# BopITSchematic.net
KiCad netlist of a schematic drawn in Altium Designer
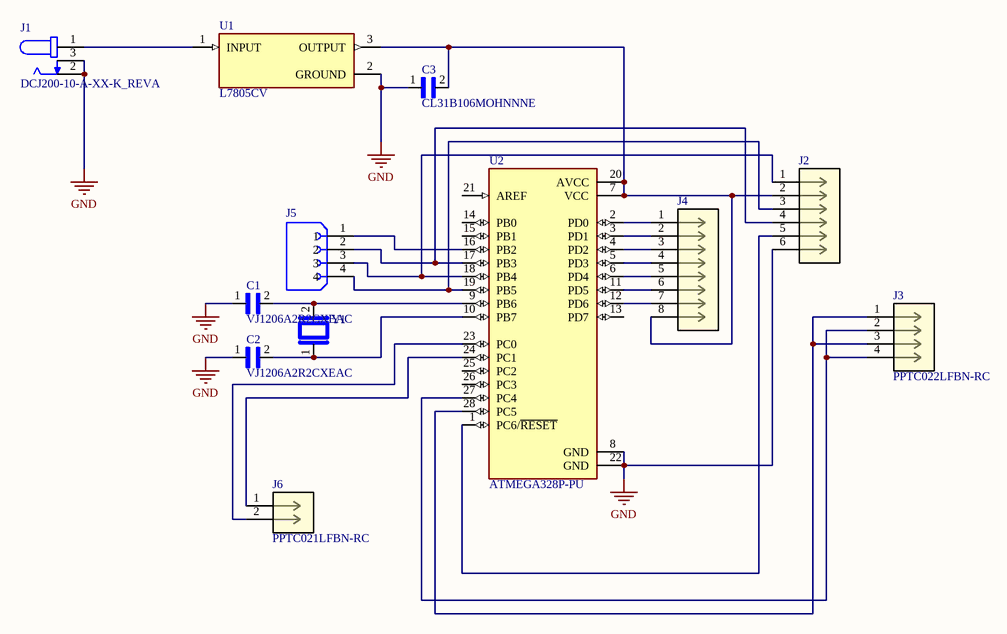
[diagram p0: BopITSchematic.SchDoc]

(export (version "E")
  (design (tool "Eeschema 10.0.6"))
  (components
    (comp (ref "C1")
      (value "VJ1206A2R2CXEAC")
      (footprint "CAPC3216X170N")
      (libsource (lib "VJ1206A2R2CXEAC") (part "VJ1206A2R2CXEAC"))
    )
    (comp (ref "C2")
      (value "VJ1206A2R2CXEAC")
      (footprint "CAPC3216X170N")
      (libsource (lib "VJ1206A2R2CXEAC") (part "VJ1206A2R2CXEAC"))
    )
    (comp (ref "C3")
      (value "CL31B106MOHNNNE")
      (footprint "CAPC3216X140N")
      (libsource (lib "CL31B106MOHNNNE") (part "CL31B106MOHNNNE"))
    )
    (comp (ref "J1")
      (value "DCJ200-10-A-XX-K_REVA")
      (footprint "GCT_DCJ200-10-A-XX-K_REVA")
      (description "Power Barrel Connector Jack 2.05mm ID (0.081), 5.50mm OD (0.217) Through Hole, Right Angle")
      (fields (field (name "MF") "Global Connector Technology") (field (name "MP") "DCJ200-10-A-K1-K"))
      (libsource (lib "DCJ200-10-A-XX-K_REVA") (part "DCJ200-10-A-XX-K_REVA"))
    )
    (comp (ref "J2")
      (value "61300621121")
      (footprint "CONN06_6130_7P62X5P08_WRE")
      (description "No Description Available")
      (libsource (lib "61300621121") (part "61300621121"))
    )
    (comp (ref "J3")
      (value "PPTC022LFBN-RC")
      (footprint "CONN_PPTC022LFBN-RC_SUL")
      (description "No Description Available")
      (libsource (lib "PPTC022LFBN-RC") (part "PPTC022LFBN-RC"))
    )
    (comp (ref "J4")
      (value "PPTC081LFBN-RC")
      (footprint "CONN_PPTC081LFBN-RC_SUL")
      (description "No Description Available")
      (libsource (lib "PPTC081LFBN-RC") (part "PPTC081LFBN-RC"))
    )
    (comp (ref "J5")
      (value "PPTC041LFBN-RC")
      (footprint "SULLINS_PPTC041LFBN-RC")
      (description "4 Position Header Connector 0.100 (2.54mm) Through Hole Tin")
      (fields (field (name "MF") "Sullins Connector") (field (name "DIGI-KEY_PART_NUMBER") "S7002-ND"))
      (libsource (lib "PPTC041LFBN-RC") (part "PPTC041LFBN-RC"))
    )
    (comp (ref "J6")
      (value "PPTC021LFBN-RC")
      (footprint "CONN2_LFBN-RC_SUL")
      (description "No Description Available")
      (libsource (lib "PPTC021LFBN-RC") (part "PPTC021LFBN-RC"))
    )
    (comp (ref "U1")
      (value "L7805CV")
      (footprint "TO255P1040X460X1968-3")
      (description "Linear Voltage Regulator IC Positive Fixed 1 Output 1.5A TO-220")
      (fields (field (name "MF") "STMicroelectronics"))
      (libsource (lib "L7805CV") (part "L7805CV"))
    )
    (comp (ref "U2")
      (value "ATMEGA328P-PU")
      (footprint "DIP794W46P254L2967H457Q28B")
      (description "ATmega Series 20 MHz 32 KB Flash 2 KB SRAM 8-Bit Microcontroller - DIP-28")
      (libsource (lib "ATMEGA328P-PU") (part "ATMEGA328P-PU"))
    )
    (comp (ref "Y1")
      (value "HC-49/U-S16000000ABJB")
      (footprint "XTAL_HC49P488W43L1150T466H350")
      (description "16 MHz Â±30ppm Crystal 18pF 50 Ohms HC-49/US")
      (fields (field (name "MF") "Citizen Finedevice Co Ltd"))
      (libsource (lib "HC-49_U-S16000000ABJB") (part "HC-49/U-S16000000ABJB"))
    )
  )
  (nets
    (net (code "1") (name "GND") (class "Default")
      (node (ref "C1") (pin "1") (pinfunction "1_1") (pintype "passive"))
      (node (ref "C2") (pin "1") (pinfunction "1_1") (pintype "passive"))
      (node (ref "C3") (pin "1") (pinfunction "1_1") (pintype "passive"))
      (node (ref "J1") (pin "2") (pinfunction "2_2") (pintype "passive"))
      (node (ref "J1") (pin "3") (pinfunction "3_3") (pintype "passive"))
      (node (ref "J2") (pin "6") (pinfunction "6_6") (pintype "passive"))
      (node (ref "U1") (pin "2") (pinfunction "GROUND_2") (pintype "power_in"))
      (node (ref "U2") (pin "22") (pinfunction "GND_22") (pintype "power_in"))
      (node (ref "U2") (pin "8") (pinfunction "GND_8") (pintype "power_in"))
    )
    (net (code "2") (name "Net-(U1-INPUT)") (class "Default")
      (node (ref "J1") (pin "1") (pinfunction "1_1") (pintype "passive"))
      (node (ref "U1") (pin "1") (pinfunction "INPUT_1") (pintype "input"))
    )
    (net (code "3") (name "Net-(U1-OUTPUT)") (class "Default")
      (node (ref "C3") (pin "2") (pinfunction "2_2") (pintype "passive"))
      (node (ref "J2") (pin "2") (pinfunction "2_2") (pintype "passive"))
      (node (ref "J4") (pin "8") (pinfunction "8_8") (pintype "passive"))
      (node (ref "U1") (pin "3") (pinfunction "OUTPUT_3") (pintype "output"))
      (node (ref "U2") (pin "20") (pinfunction "AVCC_20") (pintype "power_in"))
      (node (ref "U2") (pin "7") (pinfunction "VCC_7") (pintype "power_in"))
    )
    (net (code "4") (name "Net-(U2-PB2)") (class "Default")
      (node (ref "J5") (pin "1") (pinfunction "1_1") (pintype "passive"))
      (node (ref "U2") (pin "16") (pinfunction "PB2_16") (pintype "bidirectional"))
    )
    (net (code "5") (name "Net-(U2-PB3)") (class "Default")
      (node (ref "J2") (pin "4") (pinfunction "4_4") (pintype "passive"))
      (node (ref "J5") (pin "2") (pinfunction "2_2") (pintype "passive"))
      (node (ref "U2") (pin "17") (pinfunction "PB3_17") (pintype "bidirectional"))
    )
    (net (code "6") (name "Net-(U2-PB4)") (class "Default")
      (node (ref "J2") (pin "1") (pinfunction "1_1") (pintype "passive"))
      (node (ref "J5") (pin "3") (pinfunction "3_3") (pintype "passive"))
      (node (ref "U2") (pin "18") (pinfunction "PB4_18") (pintype "bidirectional"))
    )
    (net (code "7") (name "Net-(U2-PB5)") (class "Default")
      (node (ref "J2") (pin "3") (pinfunction "3_3") (pintype "passive"))
      (node (ref "J5") (pin "4") (pinfunction "4_4") (pintype "passive"))
      (node (ref "U2") (pin "19") (pinfunction "PB5_19") (pintype "bidirectional"))
    )
    (net (code "8") (name "Net-(U2-PB6)") (class "Default")
      (node (ref "C1") (pin "2") (pinfunction "2_2") (pintype "passive"))
      (node (ref "U2") (pin "9") (pinfunction "PB6_9") (pintype "bidirectional"))
      (node (ref "Y1") (pin "2") (pinfunction "2_2") (pintype "passive"))
    )
    (net (code "9") (name "Net-(U2-PB7)") (class "Default")
      (node (ref "C2") (pin "2") (pinfunction "2_2") (pintype "passive"))
      (node (ref "U2") (pin "10") (pinfunction "PB7_10") (pintype "bidirectional"))
      (node (ref "Y1") (pin "1") (pinfunction "1_1") (pintype "passive"))
    )
    (net (code "10") (name "Net-(U2-PC0)") (class "Default")
      (node (ref "J6") (pin "2") (pinfunction "2_2") (pintype "passive"))
      (node (ref "U2") (pin "23") (pinfunction "PC0_23") (pintype "bidirectional"))
    )
    (net (code "11") (name "Net-(U2-PC1)") (class "Default")
      (node (ref "J6") (pin "1") (pinfunction "1_1") (pintype "passive"))
      (node (ref "U2") (pin "24") (pinfunction "PC1_24") (pintype "bidirectional"))
    )
    (net (code "12") (name "Net-(U2-PC4)") (class "Default")
      (node (ref "J3") (pin "2") (pinfunction "2_2") (pintype "passive"))
      (node (ref "J3") (pin "4") (pinfunction "4_4") (pintype "passive"))
      (node (ref "U2") (pin "27") (pinfunction "PC4_27") (pintype "bidirectional"))
    )
    (net (code "13") (name "Net-(U2-PC5)") (class "Default")
      (node (ref "J3") (pin "1") (pinfunction "1_1") (pintype "passive"))
      (node (ref "J3") (pin "3") (pinfunction "3_3") (pintype "passive"))
      (node (ref "U2") (pin "28") (pinfunction "PC5_28") (pintype "bidirectional"))
    )
    (net (code "14") (name "Net-(U2-PC6{slash}~{RESET})") (class "Default")
      (node (ref "J2") (pin "5") (pinfunction "5_5") (pintype "passive"))
      (node (ref "U2") (pin "1") (pinfunction "PC6/~{RESET}_1") (pintype "bidirectional"))
    )
    (net (code "15") (name "Net-(U2-PD0)") (class "Default")
      (node (ref "J4") (pin "1") (pinfunction "1_1") (pintype "passive"))
      (node (ref "U2") (pin "2") (pinfunction "PD0_2") (pintype "bidirectional"))
    )
    (net (code "16") (name "Net-(U2-PD1)") (class "Default")
      (node (ref "J4") (pin "2") (pinfunction "2_2") (pintype "passive"))
      (node (ref "U2") (pin "3") (pinfunction "PD1_3") (pintype "bidirectional"))
    )
    (net (code "17") (name "Net-(U2-PD2)") (class "Default")
      (node (ref "J4") (pin "3") (pinfunction "3_3") (pintype "passive"))
      (node (ref "U2") (pin "4") (pinfunction "PD2_4") (pintype "bidirectional"))
    )
    (net (code "18") (name "Net-(U2-PD3)") (class "Default")
      (node (ref "J4") (pin "4") (pinfunction "4_4") (pintype "passive"))
      (node (ref "U2") (pin "5") (pinfunction "PD3_5") (pintype "bidirectional"))
    )
    (net (code "19") (name "Net-(U2-PD4)") (class "Default")
      (node (ref "J4") (pin "5") (pinfunction "5_5") (pintype "passive"))
      (node (ref "U2") (pin "6") (pinfunction "PD4_6") (pintype "bidirectional"))
    )
    (net (code "20") (name "Net-(U2-PD5)") (class "Default")
      (node (ref "J4") (pin "6") (pinfunction "6_6") (pintype "passive"))
      (node (ref "U2") (pin "11") (pinfunction "PD5_11") (pintype "bidirectional"))
    )
    (net (code "21") (name "Net-(U2-PD6)") (class "Default")
      (node (ref "J4") (pin "7") (pinfunction "7_7") (pintype "passive"))
      (node (ref "U2") (pin "12") (pinfunction "PD6_12") (pintype "bidirectional"))
    )
    (net (code "22") (name "unconnected-(U2-AREF-Pad21)") (class "Default")
      (node (ref "U2") (pin "21") (pinfunction "AREF_21") (pintype "input"))
    )
    (net (code "23") (name "unconnected-(U2-PB0-Pad14)") (class "Default")
      (node (ref "U2") (pin "14") (pinfunction "PB0_14") (pintype "bidirectional"))
    )
    (net (code "24") (name "unconnected-(U2-PB1-Pad15)") (class "Default")
      (node (ref "U2") (pin "15") (pinfunction "PB1_15") (pintype "bidirectional"))
    )
    (net (code "25") (name "unconnected-(U2-PC2-Pad25)") (class "Default")
      (node (ref "U2") (pin "25") (pinfunction "PC2_25") (pintype "bidirectional"))
    )
    (net (code "26") (name "unconnected-(U2-PC3-Pad26)") (class "Default")
      (node (ref "U2") (pin "26") (pinfunction "PC3_26") (pintype "bidirectional"))
    )
    (net (code "27") (name "unconnected-(U2-PD7-Pad13)") (class "Default")
      (node (ref "U2") (pin "13") (pinfunction "PD7_13") (pintype "bidirectional"))
    )
  )
)
